# trinKey.net
KiCad netlist of a schematic drawn in EAGLE
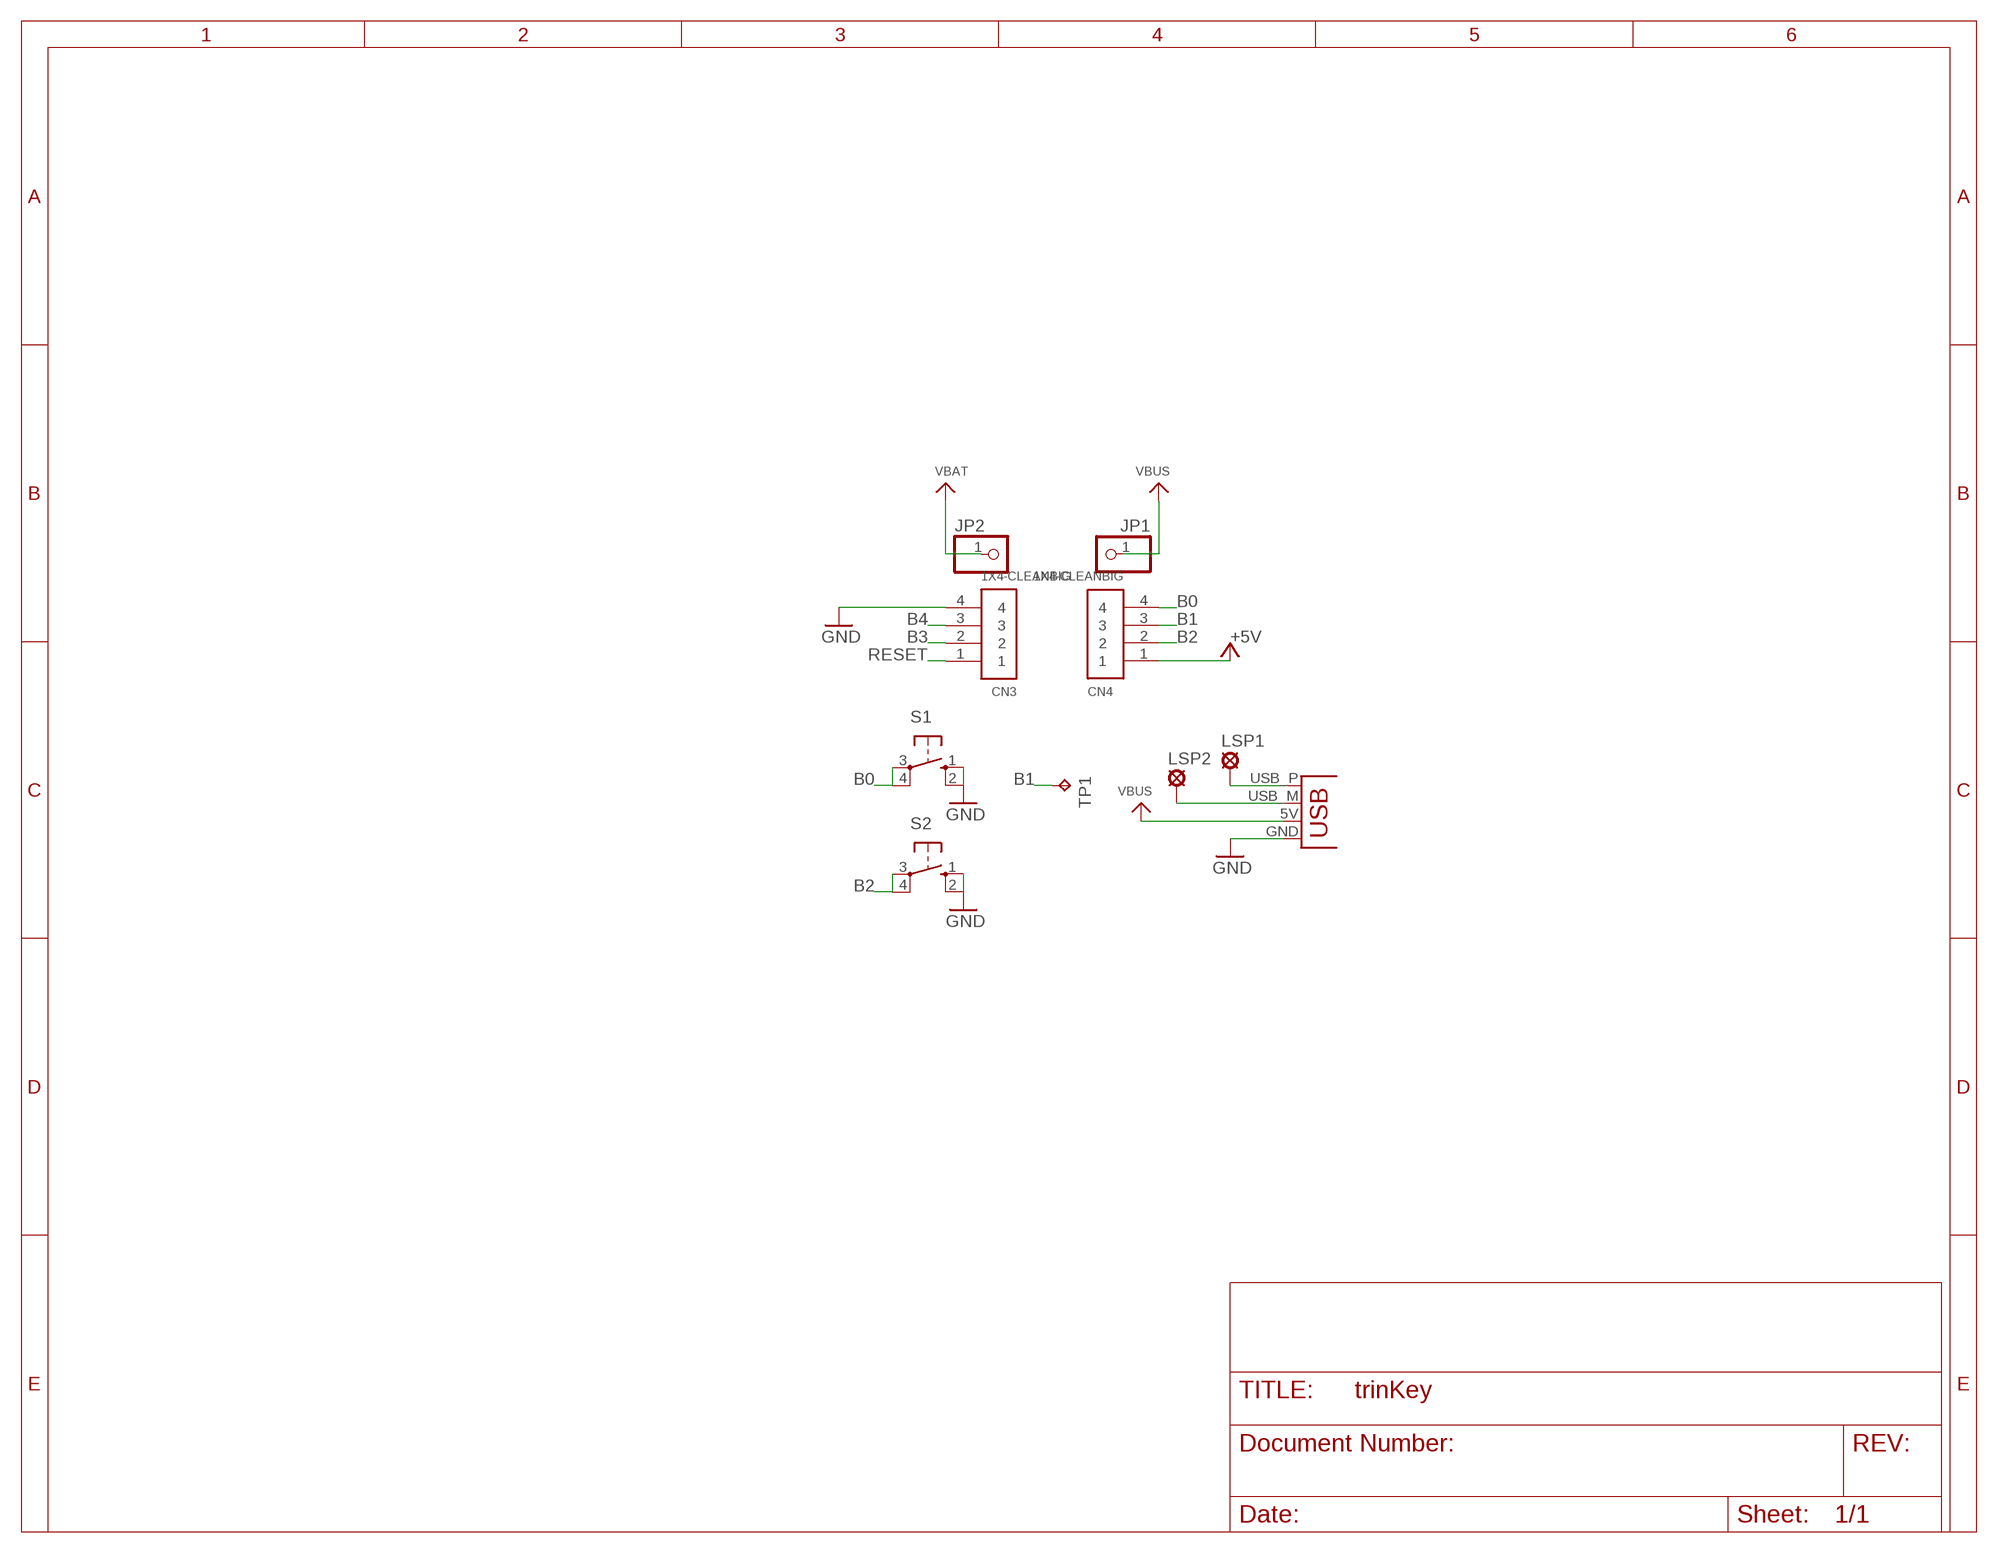
[diagram p0: schematic, sheet 1]

(export (version "E")
  (design (tool "Eeschema 10.0.6"))
  (components
    (comp (ref "CN3")
      (value "1X4-CLEANBIG")
      (footprint "eagle-import:1X04-CLEANBIG")
      (libsource (lib "eagle-import") (part "1X4-CLEANBIG"))
    )
    (comp (ref "CN4")
      (value "1X4-CLEANBIG")
      (footprint "eagle-import:1X04-CLEANBIG")
      (libsource (lib "eagle-import") (part "1X4-CLEANBIG"))
    )
    (comp (ref "JP1")
      (value "PINHD-1X1CB")
      (footprint "eagle-import:1X01-CLEANBIG")
      (libsource (lib "eagle-import") (part "PINHD-1X1CB"))
    )
    (comp (ref "JP2")
      (value "PINHD-1X1CB")
      (footprint "eagle-import:1X01-CLEANBIG")
      (libsource (lib "eagle-import") (part "PINHD-1X1CB"))
    )
    (comp (ref "JP4")
      (value "USBPCB")
      (footprint "eagle-import:USB-A-PCB")
      (libsource (lib "eagle-import") (part "USBPCB"))
    )
    (comp (ref "LSP1")
      (value "LSP10")
      (footprint "eagle-import:LSP10")
      (libsource (lib "eagle-import") (part "LSP10"))
    )
    (comp (ref "LSP2")
      (value "LSP10")
      (footprint "eagle-import:LSP10")
      (libsource (lib "eagle-import") (part "LSP10"))
    )
    (comp (ref "S1")
      (value "10-XX")
      (footprint "eagle-import:B3F-10XX")
      (fields (field (name "MPN") "B3F-1000"))
      (libsource (lib "eagle-import") (part "10-XX"))
    )
    (comp (ref "S2")
      (value "10-XX")
      (footprint "eagle-import:B3F-10XX")
      (fields (field (name "MPN") "B3F-1000"))
      (libsource (lib "eagle-import") (part "10-XX"))
    )
    (comp (ref "TP1")
      (value "TPB1,27")
      (footprint "eagle-import:B1,27")
      (libsource (lib "eagle-import") (part "TPB1,27"))
    )
  )
  (nets
    (net (code "1") (name "+5V") (class "Default")
      (node (ref "CN4") (pin "1") (pinfunction "1_1") (pintype "bidirectional"))
    )
    (net (code "2") (name "/B0") (class "Default")
      (node (ref "CN4") (pin "4") (pinfunction "4_4") (pintype "bidirectional"))
      (node (ref "S1") (pin "3") (pinfunction "P_3") (pintype "passive"))
      (node (ref "S1") (pin "4") (pinfunction "P1_4") (pintype "passive"))
    )
    (net (code "3") (name "/B1") (class "Default")
      (node (ref "CN4") (pin "3") (pinfunction "3_3") (pintype "bidirectional"))
      (node (ref "TP1") (pin "TP") (pinfunction "TP_TP") (pintype "input"))
    )
    (net (code "4") (name "/B2") (class "Default")
      (node (ref "CN4") (pin "2") (pinfunction "2_2") (pintype "bidirectional"))
      (node (ref "S2") (pin "3") (pinfunction "P_3") (pintype "passive"))
      (node (ref "S2") (pin "4") (pinfunction "P1_4") (pintype "passive"))
    )
    (net (code "5") (name "/B3") (class "Default")
      (node (ref "CN3") (pin "2") (pinfunction "2_2") (pintype "bidirectional"))
    )
    (net (code "6") (name "/B4") (class "Default")
      (node (ref "CN3") (pin "3") (pinfunction "3_3") (pintype "bidirectional"))
    )
    (net (code "7") (name "/RESET") (class "Default")
      (node (ref "CN3") (pin "1") (pinfunction "1_1") (pintype "bidirectional"))
    )
    (net (code "8") (name "GND") (class "Default")
      (node (ref "CN3") (pin "4") (pinfunction "4_4") (pintype "bidirectional"))
      (node (ref "JP4") (pin "GND") (pinfunction "GND_GND") (pintype "bidirectional"))
      (node (ref "S1") (pin "1") (pinfunction "S_1") (pintype "passive"))
      (node (ref "S1") (pin "2") (pinfunction "S1_2") (pintype "passive"))
      (node (ref "S2") (pin "1") (pinfunction "S_1") (pintype "passive"))
      (node (ref "S2") (pin "2") (pinfunction "S1_2") (pintype "passive"))
    )
    (net (code "9") (name "Net-(JP4-D+)") (class "Default")
      (node (ref "JP4") (pin "USB_P") (pinfunction "D+_USB_P") (pintype "bidirectional"))
      (node (ref "LSP1") (pin "MP") (pinfunction "MP_MP") (pintype "passive"))
    )
    (net (code "10") (name "Net-(JP4-D-)") (class "Default")
      (node (ref "JP4") (pin "USB_M") (pinfunction "D-_USB_M") (pintype "bidirectional"))
      (node (ref "LSP2") (pin "MP") (pinfunction "MP_MP") (pintype "passive"))
    )
    (net (code "11") (name "VBAT") (class "Default")
      (node (ref "JP2") (pin "1") (pinfunction "1_1") (pintype "passive"))
    )
    (net (code "12") (name "VBUS") (class "Default")
      (node (ref "JP1") (pin "1") (pinfunction "1_1") (pintype "passive"))
      (node (ref "JP4") (pin "5V") (pinfunction "VBUS_5V") (pintype "bidirectional"))
    )
  )
)
